# Regulators.net
KiCad netlist of a schematic drawn in Altium Designer
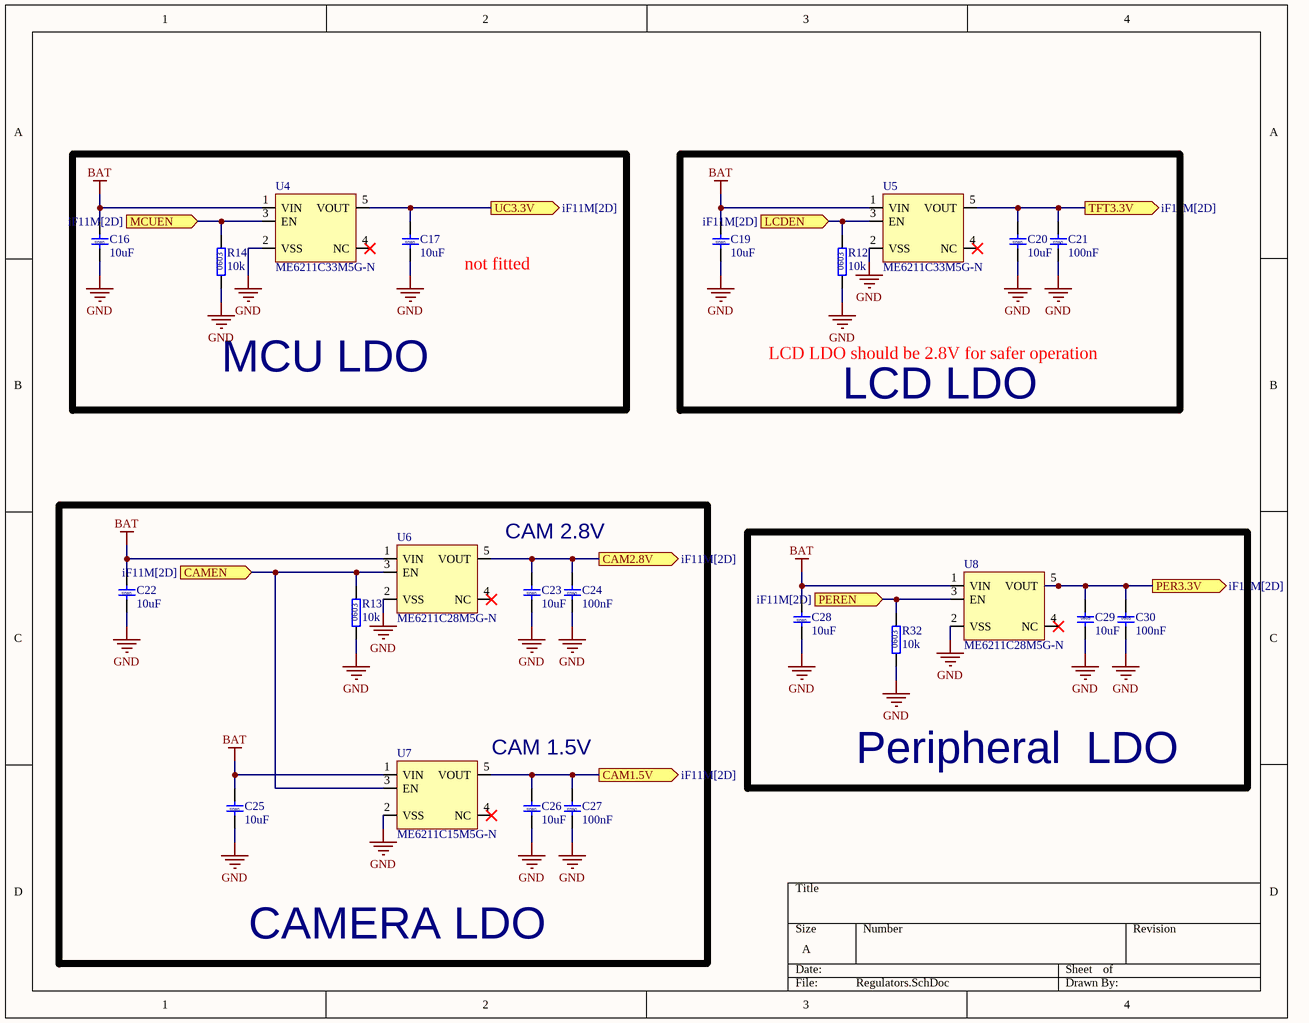
[diagram p0: Regulators.SchDoc]

(export (version "E")
  (design (tool "Eeschema 10.0.6"))
  (components
    (comp (ref "C16")
      (value "10uF")
      (footprint "C0805")
      (description "10% 25V")
      (fields (field (name "PART NO") "WP0005368"))
      (libsource (lib "Rescap") (part "C 0805 10uF 25V"))
    )
    (comp (ref "C17")
      (value "10uF")
      (footprint "C0805")
      (description "10% 25V")
      (fields (field (name "PART NO") "WP0005368"))
      (libsource (lib "Rescap") (part "C 0805 10uF 25V"))
    )
    (comp (ref "C19")
      (value "10uF")
      (footprint "C0805")
      (description "10% 25V")
      (fields (field (name "PART NO") "WP0005368"))
      (libsource (lib "Rescap") (part "C 0805 10uF 25V"))
    )
    (comp (ref "C20")
      (value "10uF")
      (footprint "C0805")
      (description "10% 25V")
      (fields (field (name "PART NO") "WP0005368"))
      (libsource (lib "Rescap") (part "C 0805 10uF 25V"))
    )
    (comp (ref "C21")
      (value "100nF")
      (footprint "C0603")
      (description "10% 50V")
      (fields (field (name "PART NO") "W-T-CA-X703N100K50VNT") (field (name "MANUFACTURER") "FENGHUA"))
      (libsource (lib "Rescap") (part "C 0603 100nF 50V"))
    )
    (comp (ref "C22")
      (value "10uF")
      (footprint "C0805")
      (description "10% 25V")
      (fields (field (name "PART NO") "WP0005368"))
      (libsource (lib "Rescap") (part "C 0805 10uF 25V"))
    )
    (comp (ref "C23")
      (value "10uF")
      (footprint "C0805")
      (description "10% 25V")
      (fields (field (name "PART NO") "WP0005368"))
      (libsource (lib "Rescap") (part "C 0805 10uF 25V"))
    )
    (comp (ref "C24")
      (value "100nF")
      (footprint "C0603")
      (description "10% 50V")
      (fields (field (name "PART NO") "W-T-CA-X703N100K50VNT") (field (name "MANUFACTURER") "FENGHUA"))
      (libsource (lib "Rescap") (part "C 0603 100nF 50V"))
    )
    (comp (ref "C25")
      (value "10uF")
      (footprint "C0805")
      (description "10% 25V")
      (fields (field (name "PART NO") "WP0005368"))
      (libsource (lib "Rescap") (part "C 0805 10uF 25V"))
    )
    (comp (ref "C26")
      (value "10uF")
      (footprint "C0805")
      (description "10% 25V")
      (fields (field (name "PART NO") "WP0005368"))
      (libsource (lib "Rescap") (part "C 0805 10uF 25V"))
    )
    (comp (ref "C27")
      (value "100nF")
      (footprint "C0603")
      (description "10% 50V")
      (fields (field (name "PART NO") "W-T-CA-X703N100K50VNT") (field (name "MANUFACTURER") "FENGHUA"))
      (libsource (lib "Rescap") (part "C 0603 100nF 50V"))
    )
    (comp (ref "C28")
      (value "10uF")
      (footprint "C0805")
      (description "10% 25V")
      (fields (field (name "PART NO") "WP0005368"))
      (libsource (lib "Rescap") (part "C 0805 10uF 25V"))
    )
    (comp (ref "C29")
      (value "10uF")
      (footprint "C0805")
      (description "10% 25V")
      (fields (field (name "PART NO") "WP0005368"))
      (libsource (lib "Rescap") (part "C 0805 10uF 25V"))
    )
    (comp (ref "C30")
      (value "100nF")
      (footprint "C0603")
      (description "10% 50V")
      (fields (field (name "PART NO") "W-T-CA-X703N100K50VNT") (field (name "MANUFACTURER") "FENGHUA"))
      (libsource (lib "Rescap") (part "C 0603 100nF 50V"))
    )
    (comp (ref "R12")
      (value "10k")
      (footprint "R0603-LD")
      (description "5%")
      (fields (field (name "PART NO") "W-T-RE-RS03K103JT") (field (name "MANUFACTURER") "热敏D541V11增加1颗用量"))
      (libsource (lib "Rescap") (part "R 0603 10k"))
    )
    (comp (ref "R13")
      (value "10k")
      (footprint "R0603-LD")
      (description "5%")
      (fields (field (name "PART NO") "W-T-RE-RS03K103JT") (field (name "MANUFACTURER") "热敏D541V11增加1颗用量"))
      (libsource (lib "Rescap") (part "R 0603 10k"))
    )
    (comp (ref "R14")
      (value "10k")
      (footprint "R0603-LD")
      (description "5%")
      (fields (field (name "PART NO") "W-T-RE-RS03K103JT") (field (name "MANUFACTURER") "热敏D541V11增加1颗用量"))
      (libsource (lib "Rescap") (part "R 0603 10k"))
    )
    (comp (ref "R32")
      (value "10k")
      (footprint "R0603-LD")
      (description "5%")
      (fields (field (name "PART NO") "W-T-RE-RS03K103JT") (field (name "MANUFACTURER") "热敏D541V11增加1颗用量"))
      (libsource (lib "Rescap") (part "R 0603 10k"))
    )
    (comp (ref "U4")
      (value "ME6211C33M5G-N")
      (footprint "SOT23-5")
      (libsource (lib "Others") (part "ME6211C28M5G"))
    )
    (comp (ref "U5")
      (value "ME6211C33M5G-N")
      (footprint "SOT23-5")
      (libsource (lib "Others") (part "ME6211C28M5G"))
    )
    (comp (ref "U6")
      (value "ME6211C28M5G-N")
      (footprint "SOT23-5")
      (libsource (lib "Others") (part "ME6211C28M5G"))
    )
    (comp (ref "U7")
      (value "ME6211C15M5G-N")
      (footprint "SOT23-5")
      (libsource (lib "Others") (part "ME6211C28M5G"))
    )
    (comp (ref "U8")
      (value "ME6211C28M5G-N")
      (footprint "SOT23-5")
      (libsource (lib "Others") (part "ME6211C28M5G"))
    )
  )
  (nets
    (net (code "1") (name "/CAM1.5V") (class "Default")
      (node (ref "C26") (pin "2") (pinfunction "2_2") (pintype "passive"))
      (node (ref "C27") (pin "2") (pinfunction "2_2") (pintype "passive"))
      (node (ref "U7") (pin "5") (pinfunction "VOUT_5") (pintype "passive"))
    )
    (net (code "2") (name "/CAM2.8V") (class "Default")
      (node (ref "C23") (pin "2") (pinfunction "2_2") (pintype "passive"))
      (node (ref "C24") (pin "2") (pinfunction "2_2") (pintype "passive"))
      (node (ref "U6") (pin "5") (pinfunction "VOUT_5") (pintype "passive"))
    )
    (net (code "3") (name "/CAMEN") (class "Default")
      (node (ref "R13") (pin "2") (pinfunction "2_2") (pintype "passive"))
      (node (ref "U6") (pin "3") (pinfunction "EN_3") (pintype "passive"))
      (node (ref "U7") (pin "3") (pinfunction "EN_3") (pintype "passive"))
    )
    (net (code "4") (name "/LCDEN") (class "Default")
      (node (ref "R12") (pin "2") (pinfunction "2_2") (pintype "passive"))
      (node (ref "U5") (pin "3") (pinfunction "EN_3") (pintype "passive"))
    )
    (net (code "5") (name "/MCUEN") (class "Default")
      (node (ref "R14") (pin "2") (pinfunction "2_2") (pintype "passive"))
      (node (ref "U4") (pin "3") (pinfunction "EN_3") (pintype "passive"))
    )
    (net (code "6") (name "/PER3.3V") (class "Default")
      (node (ref "C29") (pin "1") (pinfunction "1_1") (pintype "passive"))
      (node (ref "C30") (pin "1") (pinfunction "1_1") (pintype "passive"))
      (node (ref "U8") (pin "5") (pinfunction "VOUT_5") (pintype "passive"))
    )
    (net (code "7") (name "/PEREN") (class "Default")
      (node (ref "R32") (pin "2") (pinfunction "2_2") (pintype "passive"))
      (node (ref "U8") (pin "3") (pinfunction "EN_3") (pintype "passive"))
    )
    (net (code "8") (name "/TFT3.3V") (class "Default")
      (node (ref "C20") (pin "2") (pinfunction "2_2") (pintype "passive"))
      (node (ref "C21") (pin "2") (pinfunction "2_2") (pintype "passive"))
      (node (ref "U5") (pin "5") (pinfunction "VOUT_5") (pintype "passive"))
    )
    (net (code "9") (name "/UC3.3V") (class "Default")
      (node (ref "C17") (pin "2") (pinfunction "2_2") (pintype "passive"))
      (node (ref "U4") (pin "5") (pinfunction "VOUT_5") (pintype "passive"))
    )
    (net (code "10") (name "BAT") (class "Default")
      (node (ref "C16") (pin "2") (pinfunction "2_2") (pintype "passive"))
      (node (ref "C19") (pin "2") (pinfunction "2_2") (pintype "passive"))
      (node (ref "C22") (pin "2") (pinfunction "2_2") (pintype "passive"))
      (node (ref "C25") (pin "2") (pinfunction "2_2") (pintype "passive"))
      (node (ref "C28") (pin "2") (pinfunction "2_2") (pintype "passive"))
      (node (ref "U4") (pin "1") (pinfunction "VIN_1") (pintype "passive"))
      (node (ref "U5") (pin "1") (pinfunction "VIN_1") (pintype "passive"))
      (node (ref "U6") (pin "1") (pinfunction "VIN_1") (pintype "passive"))
      (node (ref "U7") (pin "1") (pinfunction "VIN_1") (pintype "passive"))
      (node (ref "U8") (pin "1") (pinfunction "VIN_1") (pintype "passive"))
    )
    (net (code "11") (name "GND") (class "Default")
      (node (ref "C16") (pin "1") (pinfunction "1_1") (pintype "passive"))
      (node (ref "C17") (pin "1") (pinfunction "1_1") (pintype "passive"))
      (node (ref "C19") (pin "1") (pinfunction "1_1") (pintype "passive"))
      (node (ref "C20") (pin "1") (pinfunction "1_1") (pintype "passive"))
      (node (ref "C21") (pin "1") (pinfunction "1_1") (pintype "passive"))
      (node (ref "C22") (pin "1") (pinfunction "1_1") (pintype "passive"))
      (node (ref "C23") (pin "1") (pinfunction "1_1") (pintype "passive"))
      (node (ref "C24") (pin "1") (pinfunction "1_1") (pintype "passive"))
      (node (ref "C25") (pin "1") (pinfunction "1_1") (pintype "passive"))
      (node (ref "C26") (pin "1") (pinfunction "1_1") (pintype "passive"))
      (node (ref "C27") (pin "1") (pinfunction "1_1") (pintype "passive"))
      (node (ref "C28") (pin "1") (pinfunction "1_1") (pintype "passive"))
      (node (ref "C29") (pin "2") (pinfunction "2_2") (pintype "passive"))
      (node (ref "C30") (pin "2") (pinfunction "2_2") (pintype "passive"))
      (node (ref "R12") (pin "1") (pinfunction "1_1") (pintype "passive"))
      (node (ref "R13") (pin "1") (pinfunction "1_1") (pintype "passive"))
      (node (ref "R14") (pin "1") (pinfunction "1_1") (pintype "passive"))
      (node (ref "R32") (pin "1") (pinfunction "1_1") (pintype "passive"))
      (node (ref "U4") (pin "2") (pinfunction "VSS_2") (pintype "passive"))
      (node (ref "U5") (pin "2") (pinfunction "VSS_2") (pintype "passive"))
      (node (ref "U6") (pin "2") (pinfunction "VSS_2") (pintype "passive"))
      (node (ref "U7") (pin "2") (pinfunction "VSS_2") (pintype "passive"))
      (node (ref "U8") (pin "2") (pinfunction "VSS_2") (pintype "passive"))
    )
    (net (code "12") (name "unconnected-(U4-NC-Pad4)") (class "Default")
      (node (ref "U4") (pin "4") (pinfunction "NC_4") (pintype "passive+no_connect"))
    )
    (net (code "13") (name "unconnected-(U5-NC-Pad4)") (class "Default")
      (node (ref "U5") (pin "4") (pinfunction "NC_4") (pintype "passive+no_connect"))
    )
    (net (code "14") (name "unconnected-(U6-NC-Pad4)") (class "Default")
      (node (ref "U6") (pin "4") (pinfunction "NC_4") (pintype "passive+no_connect"))
    )
    (net (code "15") (name "unconnected-(U7-NC-Pad4)") (class "Default")
      (node (ref "U7") (pin "4") (pinfunction "NC_4") (pintype "passive+no_connect"))
    )
    (net (code "16") (name "unconnected-(U8-NC-Pad4)") (class "Default")
      (node (ref "U8") (pin "4") (pinfunction "NC_4") (pintype "passive+no_connect"))
    )
  )
)
